# OpenProg-18F2550.net
KiCad netlist of a schematic drawn in EAGLE
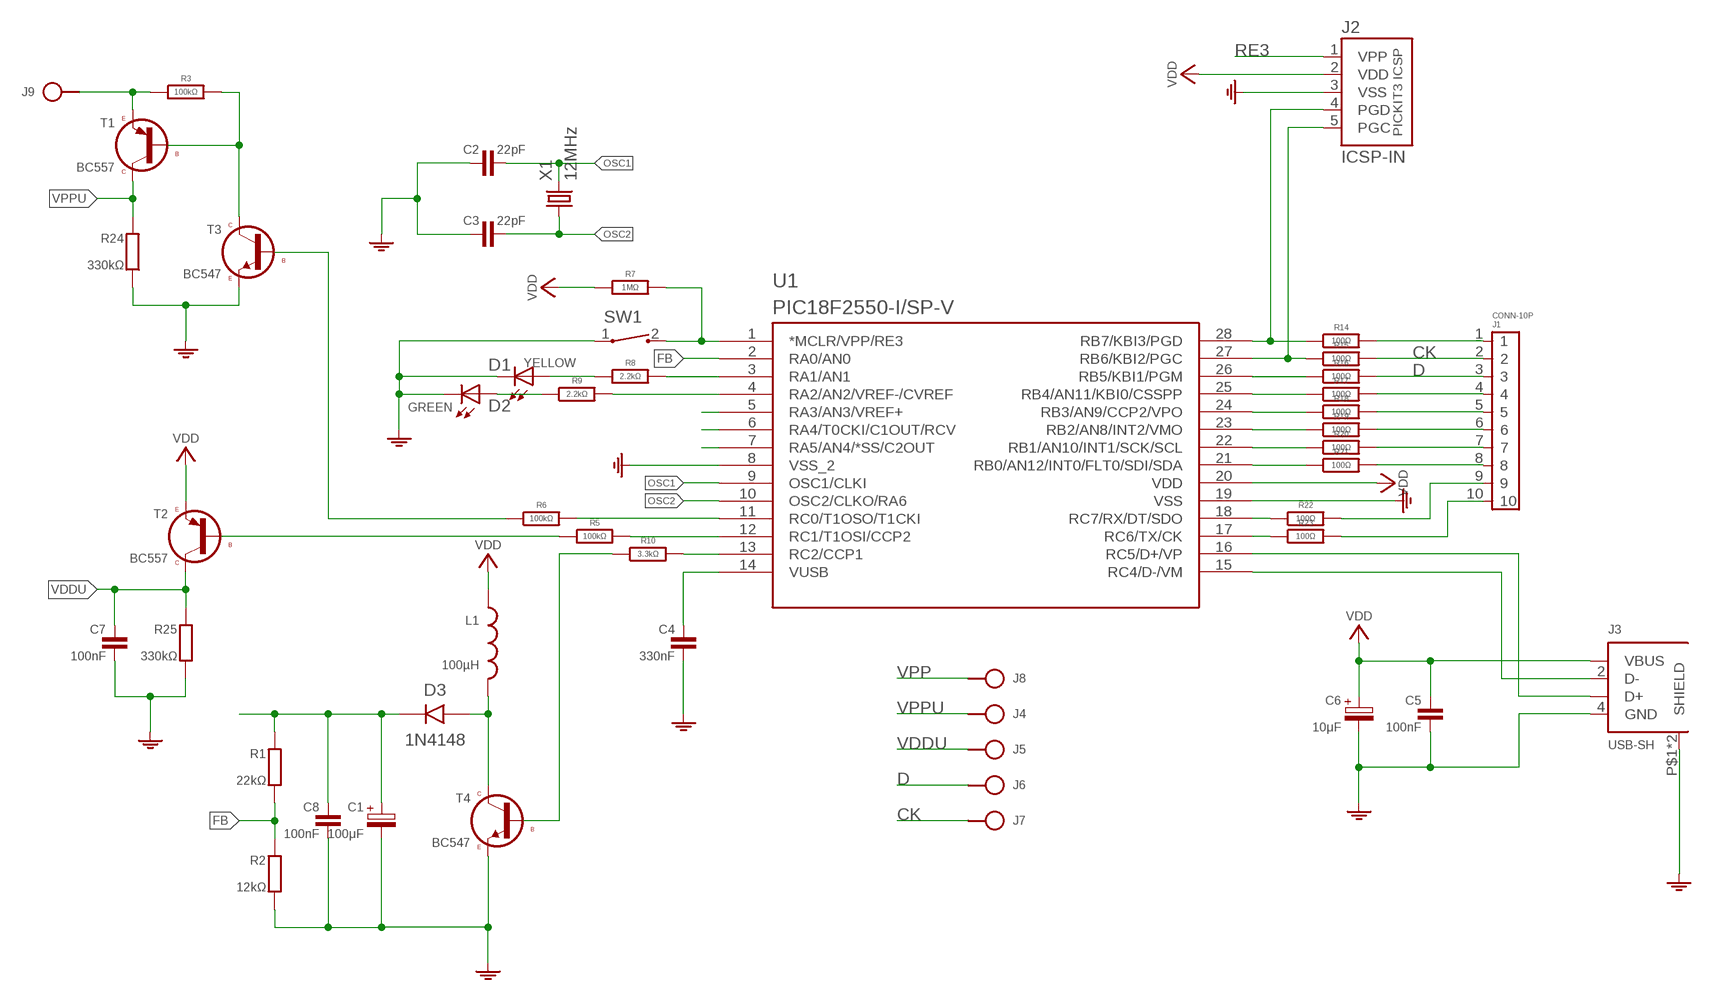
[diagram p0: schematic, sheet 1]

(export (version "E")
  (design (tool "Eeschema 10.0.6"))
  (components
    (comp (ref "C1")
      (value "100μF")
      (footprint "eagle-import:E5-5")
      (libsource (lib "eagle-import") (part "CPOLE5-5"))
    )
    (comp (ref "C2")
      (value "22pF")
      (footprint "eagle-import:C025-015X024")
      (libsource (lib "eagle-import") (part "C-H025-015X024"))
    )
    (comp (ref "C3")
      (value "22pF")
      (footprint "eagle-import:C025-015X024")
      (libsource (lib "eagle-import") (part "C-H025-015X024"))
    )
    (comp (ref "C4")
      (value "330nF")
      (footprint "eagle-import:C050-030X075")
      (libsource (lib "eagle-import") (part "C050-030X075"))
    )
    (comp (ref "C5")
      (value "100nF")
      (footprint "eagle-import:C050-025X075")
      (libsource (lib "eagle-import") (part "C050-025X075"))
    )
    (comp (ref "C6")
      (value "10μF")
      (footprint "eagle-import:E5-5")
      (libsource (lib "eagle-import") (part "CPOLE5-5"))
    )
    (comp (ref "C7")
      (value "100nF")
      (footprint "eagle-import:C050-025X075")
      (libsource (lib "eagle-import") (part "C050-025X075"))
    )
    (comp (ref "C8")
      (value "100nF")
      (footprint "eagle-import:C050-025X075")
      (libsource (lib "eagle-import") (part "C050-025X075"))
    )
    (comp (ref "D1")
      (value "YELLOW")
      (footprint "eagle-import:LED_3MM")
      (libsource (lib "eagle-import") (part "LED-3MM"))
    )
    (comp (ref "D2")
      (value "GREEN")
      (footprint "eagle-import:LED_3MM")
      (libsource (lib "eagle-import") (part "LED-3MM"))
    )
    (comp (ref "D3")
      (value "1N4148")
      (footprint "eagle-import:DO34-7")
      (libsource (lib "eagle-import") (part "1N4148-HDO34-7"))
    )
    (comp (ref "J1")
      (value "CONN-10P")
      (footprint "eagle-import:CONN-10P")
      (libsource (lib "eagle-import") (part "CONN-10P"))
    )
    (comp (ref "J2")
      (value "ICSP-IN")
      (footprint "eagle-import:PIC-PK3")
      (libsource (lib "eagle-import") (part "PICKIT3-ICSP-PK3"))
    )
    (comp (ref "J3")
      (value "USB-SH")
      (footprint "eagle-import:USB-B-PRINT")
      (libsource (lib "eagle-import") (part "USB-SH"))
    )
    (comp (ref "J4")
      (value "HPORT")
      (footprint "eagle-import:SPAD")
      (libsource (lib "eagle-import") (part "HPORT"))
    )
    (comp (ref "J5")
      (value "HPORT")
      (footprint "eagle-import:SPAD")
      (libsource (lib "eagle-import") (part "HPORT"))
    )
    (comp (ref "J6")
      (value "HPORT")
      (footprint "eagle-import:SPAD")
      (libsource (lib "eagle-import") (part "HPORT"))
    )
    (comp (ref "J7")
      (value "HPORT")
      (footprint "eagle-import:SPAD")
      (libsource (lib "eagle-import") (part "HPORT"))
    )
    (comp (ref "J8")
      (value "HPORT")
      (footprint "eagle-import:SPAD")
      (libsource (lib "eagle-import") (part "HPORT"))
    )
    (comp (ref "J9")
      (value "HPORT")
      (footprint "eagle-import:SPAD")
      (libsource (lib "eagle-import") (part "HPORT"))
    )
    (comp (ref "L1")
      (value "100µH")
      (footprint "eagle-import:L-03_10V")
      (libsource (lib "eagle-import") (part "L02/10"))
    )
    (comp (ref "R1")
      (value "22kΩ")
      (footprint "eagle-import:0204_10-V")
      (libsource (lib "eagle-import") (part "R0204/10-V"))
    )
    (comp (ref "R2")
      (value "12kΩ")
      (footprint "eagle-import:0204_10-V")
      (libsource (lib "eagle-import") (part "R0204/10-V"))
    )
    (comp (ref "R3")
      (value "100kΩ")
      (footprint "eagle-import:0204_2")
      (libsource (lib "eagle-import") (part "R-H0204/2"))
    )
    (comp (ref "R5")
      (value "100kΩ")
      (footprint "eagle-import:0204_10")
      (libsource (lib "eagle-import") (part "R-H0204/10"))
    )
    (comp (ref "R6")
      (value "100kΩ")
      (footprint "eagle-import:0204_10")
      (libsource (lib "eagle-import") (part "R-H0204/10"))
    )
    (comp (ref "R7")
      (value "1MΩ")
      (footprint "eagle-import:0204_10")
      (libsource (lib "eagle-import") (part "R-H0204/10"))
    )
    (comp (ref "R8")
      (value "2.2kΩ")
      (footprint "eagle-import:0204_10")
      (libsource (lib "eagle-import") (part "R-H0204/10"))
    )
    (comp (ref "R9")
      (value "2.2kΩ")
      (footprint "eagle-import:0204_10")
      (libsource (lib "eagle-import") (part "R-H0204/10"))
    )
    (comp (ref "R10")
      (value "3.3kΩ")
      (footprint "eagle-import:0204_10")
      (libsource (lib "eagle-import") (part "R-H0204/10"))
    )
    (comp (ref "R14")
      (value "100Ω")
      (footprint "eagle-import:0204_10")
      (libsource (lib "eagle-import") (part "R-H0204/10"))
    )
    (comp (ref "R15")
      (value "100Ω")
      (footprint "eagle-import:0204_10")
      (libsource (lib "eagle-import") (part "R-H0204/10"))
    )
    (comp (ref "R16")
      (value "100Ω")
      (footprint "eagle-import:0204_10")
      (libsource (lib "eagle-import") (part "R-H0204/10"))
    )
    (comp (ref "R17")
      (value "100Ω")
      (footprint "eagle-import:0204_10")
      (libsource (lib "eagle-import") (part "R-H0204/10"))
    )
    (comp (ref "R18")
      (value "100Ω")
      (footprint "eagle-import:0204_10")
      (libsource (lib "eagle-import") (part "R-H0204/10"))
    )
    (comp (ref "R19")
      (value "100Ω")
      (footprint "eagle-import:0204_10")
      (libsource (lib "eagle-import") (part "R-H0204/10"))
    )
    (comp (ref "R20")
      (value "100Ω")
      (footprint "eagle-import:0204_10")
      (libsource (lib "eagle-import") (part "R-H0204/10"))
    )
    (comp (ref "R21")
      (value "100Ω")
      (footprint "eagle-import:0204_10")
      (libsource (lib "eagle-import") (part "R-H0204/10"))
    )
    (comp (ref "R22")
      (value "100Ω")
      (footprint "eagle-import:0204_10")
      (libsource (lib "eagle-import") (part "R-H0204/10"))
    )
    (comp (ref "R23")
      (value "100Ω")
      (footprint "eagle-import:0204_10")
      (libsource (lib "eagle-import") (part "R-H0204/10"))
    )
    (comp (ref "R24")
      (value "330kΩ")
      (footprint "eagle-import:0204_10-V")
      (libsource (lib "eagle-import") (part "R0204/10-V"))
    )
    (comp (ref "R25")
      (value "330kΩ")
      (footprint "eagle-import:0204_10-V")
      (libsource (lib "eagle-import") (part "R0204/10-V"))
    )
    (comp (ref "SW1")
      (value "PUSHBUTTON-P1T")
      (footprint "eagle-import:PB-1P1T")
      (libsource (lib "eagle-import") (part "PUSHBUTTON-P1T"))
    )
    (comp (ref "T1")
      (value "BC557")
      (footprint "eagle-import:TO92-CBE-A")
      (libsource (lib "eagle-import") (part "BC557CBE-A"))
    )
    (comp (ref "T2")
      (value "BC557")
      (footprint "eagle-import:TO92-CBE-A")
      (libsource (lib "eagle-import") (part "BC557CBE-A"))
    )
    (comp (ref "T3")
      (value "BC547")
      (footprint "eagle-import:TO92-CBE-A")
      (libsource (lib "eagle-import") (part "BC547-A"))
    )
    (comp (ref "T4")
      (value "BC547")
      (footprint "eagle-import:TO92-CBE-A")
      (libsource (lib "eagle-import") (part "BC547-A"))
    )
    (comp (ref "U1")
      (value "PIC18F2550-I/SP-V")
      (footprint "eagle-import:DIL28-3_V")
      (libsource (lib "eagle-import") (part "PIC18F2550-I/SP-V"))
    )
    (comp (ref "X1")
      (value "12MHz")
      (footprint "eagle-import:HC49")
      (libsource (lib "eagle-import") (part "CRYSTALHC49"))
    )
  )
  (nets
    (net (code "1") (name "/CK") (class "Default")
      (node (ref "J1") (pin "2") (pinfunction "2_2") (pintype "passive"))
      (node (ref "J7") (pin "1") (pinfunction "P$1_1") (pintype "passive"))
      (node (ref "R15") (pin "2") (pinfunction "2_2") (pintype "passive"))
    )
    (net (code "2") (name "/D") (class "Default")
      (node (ref "J1") (pin "3") (pinfunction "3_3") (pintype "passive"))
      (node (ref "J6") (pin "1") (pinfunction "P$1_1") (pintype "passive"))
      (node (ref "R16") (pin "2") (pinfunction "2_2") (pintype "passive"))
    )
    (net (code "3") (name "/RE3") (class "Default")
      (node (ref "J2") (pin "1") (pinfunction "VPP_1") (pintype "passive"))
      (node (ref "R7") (pin "2") (pinfunction "2_2") (pintype "passive"))
      (node (ref "SW1") (pin "2") (pinfunction "2_2") (pintype "passive"))
      (node (ref "U1") (pin "1") (pinfunction "*MCLR/VPP/RE3_1") (pintype "passive"))
    )
    (net (code "4") (name "/VPP") (class "Default")
      (node (ref "C1") (pin "+") (pinfunction "+_+") (pintype "passive"))
      (node (ref "C8") (pin "1") (pinfunction "1_1") (pintype "passive"))
      (node (ref "D3") (pin "C") (pinfunction "C_C") (pintype "passive"))
      (node (ref "J8") (pin "1") (pinfunction "P$1_1") (pintype "passive"))
      (node (ref "R1") (pin "1") (pinfunction "2_1") (pintype "passive"))
    )
    (net (code "5") (name "FB") (class "Default")
      (node (ref "R1") (pin "2") (pinfunction "1_2") (pintype "passive"))
      (node (ref "R2") (pin "1") (pinfunction "2_1") (pintype "passive"))
      (node (ref "U1") (pin "2") (pinfunction "RA0/AN0_2") (pintype "passive"))
    )
    (net (code "6") (name "GND") (class "Default")
      (node (ref "C1") (pin "-") (pinfunction "-_-") (pintype "passive"))
      (node (ref "C2") (pin "1") (pinfunction "1_1") (pintype "passive"))
      (node (ref "C3") (pin "1") (pinfunction "1_1") (pintype "passive"))
      (node (ref "C4") (pin "2") (pinfunction "2_2") (pintype "passive"))
      (node (ref "C5") (pin "2") (pinfunction "2_2") (pintype "passive"))
      (node (ref "C6") (pin "-") (pinfunction "-_-") (pintype "passive"))
      (node (ref "C7") (pin "2") (pinfunction "2_2") (pintype "passive"))
      (node (ref "C8") (pin "2") (pinfunction "2_2") (pintype "passive"))
      (node (ref "D1") (pin "K") (pinfunction "C_K") (pintype "passive"))
      (node (ref "D2") (pin "K") (pinfunction "C_K") (pintype "passive"))
      (node (ref "J2") (pin "3") (pinfunction "VSS_3") (pintype "passive"))
      (node (ref "J3") (pin "4") (pinfunction "GND_4") (pintype "bidirectional"))
      (node (ref "J3") (pin "P$1") (pinfunction "SHIELD_P$1") (pintype "bidirectional"))
      (node (ref "J3") (pin "P$2") (pinfunction "SHIELD_P$2") (pintype "bidirectional"))
      (node (ref "R2") (pin "2") (pinfunction "1_2") (pintype "passive"))
      (node (ref "R24") (pin "2") (pinfunction "1_2") (pintype "passive"))
      (node (ref "R25") (pin "2") (pinfunction "1_2") (pintype "passive"))
      (node (ref "SW1") (pin "1") (pinfunction "1_1") (pintype "passive"))
      (node (ref "T3") (pin "3") (pinfunction "E_3") (pintype "passive"))
      (node (ref "T4") (pin "3") (pinfunction "E_3") (pintype "passive"))
      (node (ref "U1") (pin "19") (pinfunction "VSS_19") (pintype "passive"))
      (node (ref "U1") (pin "8") (pinfunction "VSS_2_8") (pintype "passive"))
    )
    (net (code "7") (name "Net-(D1-PadA)") (class "Default")
      (node (ref "D1") (pin "A") (pinfunction "A_A") (pintype "passive"))
      (node (ref "R8") (pin "1") (pinfunction "1_1") (pintype "passive"))
    )
    (net (code "8") (name "Net-(D2-PadA)") (class "Default")
      (node (ref "D2") (pin "A") (pinfunction "A_A") (pintype "passive"))
      (node (ref "R9") (pin "1") (pinfunction "1_1") (pintype "passive"))
    )
    (net (code "9") (name "Net-(J1-Pad1)") (class "Default")
      (node (ref "J1") (pin "1") (pinfunction "1_1") (pintype "passive"))
      (node (ref "R14") (pin "2") (pinfunction "2_2") (pintype "passive"))
    )
    (net (code "10") (name "Net-(J1-Pad4)") (class "Default")
      (node (ref "J1") (pin "4") (pinfunction "4_4") (pintype "passive"))
      (node (ref "R17") (pin "2") (pinfunction "2_2") (pintype "passive"))
    )
    (net (code "11") (name "Net-(J1-Pad5)") (class "Default")
      (node (ref "J1") (pin "5") (pinfunction "5_5") (pintype "passive"))
      (node (ref "R18") (pin "2") (pinfunction "2_2") (pintype "passive"))
    )
    (net (code "12") (name "Net-(J1-Pad6)") (class "Default")
      (node (ref "J1") (pin "6") (pinfunction "6_6") (pintype "passive"))
      (node (ref "R19") (pin "2") (pinfunction "2_2") (pintype "passive"))
    )
    (net (code "13") (name "Net-(J1-Pad7)") (class "Default")
      (node (ref "J1") (pin "7") (pinfunction "7_7") (pintype "passive"))
      (node (ref "R20") (pin "2") (pinfunction "2_2") (pintype "passive"))
    )
    (net (code "14") (name "Net-(J1-Pad8)") (class "Default")
      (node (ref "J1") (pin "8") (pinfunction "8_8") (pintype "passive"))
      (node (ref "R21") (pin "2") (pinfunction "2_2") (pintype "passive"))
    )
    (net (code "15") (name "Net-(J1-Pad9)") (class "Default")
      (node (ref "J1") (pin "9") (pinfunction "9_9") (pintype "passive"))
      (node (ref "R22") (pin "2") (pinfunction "2_2") (pintype "passive"))
    )
    (net (code "16") (name "Net-(J1-Pad10)") (class "Default")
      (node (ref "J1") (pin "10") (pinfunction "10_10") (pintype "passive"))
      (node (ref "R23") (pin "2") (pinfunction "2_2") (pintype "passive"))
    )
    (net (code "17") (name "Net-(J2-PGC)") (class "Default")
      (node (ref "J2") (pin "5") (pinfunction "PGC_5") (pintype "passive"))
      (node (ref "R15") (pin "1") (pinfunction "1_1") (pintype "passive"))
      (node (ref "U1") (pin "27") (pinfunction "RB6/KBI2/PGC_27") (pintype "passive"))
    )
    (net (code "18") (name "Net-(J2-PGD)") (class "Default")
      (node (ref "J2") (pin "4") (pinfunction "PGD_4") (pintype "passive"))
      (node (ref "R14") (pin "1") (pinfunction "1_1") (pintype "passive"))
      (node (ref "U1") (pin "28") (pinfunction "RB7/KBI3/PGD_28") (pintype "passive"))
    )
    (net (code "19") (name "Net-(J3-D+)") (class "Default")
      (node (ref "J3") (pin "3") (pinfunction "D+_3") (pintype "bidirectional"))
      (node (ref "U1") (pin "16") (pinfunction "RC5/D+/VP_16") (pintype "passive"))
    )
    (net (code "20") (name "Net-(J3-D-)") (class "Default")
      (node (ref "J3") (pin "2") (pinfunction "D-_2") (pintype "bidirectional"))
      (node (ref "U1") (pin "15") (pinfunction "RC4/D-/VM_15") (pintype "passive"))
    )
    (net (code "21") (name "Net-(J9-P$1)") (class "Default")
      (node (ref "J9") (pin "1") (pinfunction "P$1_1") (pintype "passive"))
      (node (ref "R3") (pin "1") (pinfunction "1_1") (pintype "passive"))
      (node (ref "T1") (pin "3") (pinfunction "E_3") (pintype "passive"))
    )
    (net (code "22") (name "Net-(T1-B)") (class "Default")
      (node (ref "R3") (pin "2") (pinfunction "2_2") (pintype "passive"))
      (node (ref "T1") (pin "2") (pinfunction "B_2") (pintype "passive"))
      (node (ref "T3") (pin "1") (pinfunction "C_1") (pintype "passive"))
    )
    (net (code "23") (name "Net-(T2-B)") (class "Default")
      (node (ref "R5") (pin "1") (pinfunction "1_1") (pintype "passive"))
      (node (ref "T2") (pin "2") (pinfunction "B_2") (pintype "passive"))
    )
    (net (code "24") (name "Net-(T3-B)") (class "Default")
      (node (ref "R6") (pin "1") (pinfunction "1_1") (pintype "passive"))
      (node (ref "T3") (pin "2") (pinfunction "B_2") (pintype "passive"))
    )
    (net (code "25") (name "Net-(T4-B)") (class "Default")
      (node (ref "R10") (pin "1") (pinfunction "1_1") (pintype "passive"))
      (node (ref "T4") (pin "2") (pinfunction "B_2") (pintype "passive"))
    )
    (net (code "26") (name "Net-(T4-C)") (class "Default")
      (node (ref "D3") (pin "A") (pinfunction "A_A") (pintype "passive"))
      (node (ref "L1") (pin "2") (pinfunction "2_2") (pintype "passive"))
      (node (ref "T4") (pin "1") (pinfunction "C_1") (pintype "passive"))
    )
    (net (code "27") (name "Net-(U1-RA1{slash}AN1)") (class "Default")
      (node (ref "R8") (pin "2") (pinfunction "2_2") (pintype "passive"))
      (node (ref "U1") (pin "3") (pinfunction "RA1/AN1_3") (pintype "passive"))
    )
    (net (code "28") (name "Net-(U1-RA2{slash}AN2{slash}VREF-{slash}CVREF)") (class "Default")
      (node (ref "R9") (pin "2") (pinfunction "2_2") (pintype "passive"))
      (node (ref "U1") (pin "4") (pinfunction "RA2/AN2/VREF-/CVREF_4") (pintype "passive"))
    )
    (net (code "29") (name "Net-(U1-RB0{slash}AN12{slash}INT0{slash}FLT0{slash}SDI{slash}SDA)") (class "Default")
      (node (ref "R21") (pin "1") (pinfunction "1_1") (pintype "passive"))
      (node (ref "U1") (pin "21") (pinfunction "RB0/AN12/INT0/FLT0/SDI/SDA_21") (pintype "passive"))
    )
    (net (code "30") (name "Net-(U1-RB1{slash}AN10{slash}INT1{slash}SCK{slash}SCL)") (class "Default")
      (node (ref "R20") (pin "1") (pinfunction "1_1") (pintype "passive"))
      (node (ref "U1") (pin "22") (pinfunction "RB1/AN10/INT1/SCK/SCL_22") (pintype "passive"))
    )
    (net (code "31") (name "Net-(U1-RB2{slash}AN8{slash}INT2{slash}VMO)") (class "Default")
      (node (ref "R19") (pin "1") (pinfunction "1_1") (pintype "passive"))
      (node (ref "U1") (pin "23") (pinfunction "RB2/AN8/INT2/VMO_23") (pintype "passive"))
    )
    (net (code "32") (name "Net-(U1-RB3{slash}AN9{slash}CCP2{slash}VPO)") (class "Default")
      (node (ref "R18") (pin "1") (pinfunction "1_1") (pintype "passive"))
      (node (ref "U1") (pin "24") (pinfunction "RB3/AN9/CCP2/VPO_24") (pintype "passive"))
    )
    (net (code "33") (name "Net-(U1-RB4{slash}AN11{slash}KBI0{slash}CSSPP)") (class "Default")
      (node (ref "R17") (pin "1") (pinfunction "1_1") (pintype "passive"))
      (node (ref "U1") (pin "25") (pinfunction "RB4/AN11/KBI0/CSSPP_25") (pintype "passive"))
    )
    (net (code "34") (name "Net-(U1-RB5{slash}KBI1{slash}PGM)") (class "Default")
      (node (ref "R16") (pin "1") (pinfunction "1_1") (pintype "passive"))
      (node (ref "U1") (pin "26") (pinfunction "RB5/KBI1/PGM_26") (pintype "passive"))
    )
    (net (code "35") (name "Net-(U1-RC0{slash}T1OSO{slash}T1CKI)") (class "Default")
      (node (ref "R6") (pin "2") (pinfunction "2_2") (pintype "passive"))
      (node (ref "U1") (pin "11") (pinfunction "RC0/T1OSO/T1CKI_11") (pintype "passive"))
    )
    (net (code "36") (name "Net-(U1-RC1{slash}T1OSI{slash}CCP2)") (class "Default")
      (node (ref "R5") (pin "2") (pinfunction "2_2") (pintype "passive"))
      (node (ref "U1") (pin "12") (pinfunction "RC1/T1OSI/CCP2_12") (pintype "passive"))
    )
    (net (code "37") (name "Net-(U1-RC2{slash}CCP1)") (class "Default")
      (node (ref "R10") (pin "2") (pinfunction "2_2") (pintype "passive"))
      (node (ref "U1") (pin "13") (pinfunction "RC2/CCP1_13") (pintype "passive"))
    )
    (net (code "38") (name "Net-(U1-RC6{slash}TX{slash}CK)") (class "Default")
      (node (ref "R23") (pin "1") (pinfunction "1_1") (pintype "passive"))
      (node (ref "U1") (pin "17") (pinfunction "RC6/TX/CK_17") (pintype "passive"))
    )
    (net (code "39") (name "Net-(U1-RC7{slash}RX{slash}DT{slash}SDO)") (class "Default")
      (node (ref "R22") (pin "1") (pinfunction "1_1") (pintype "passive"))
      (node (ref "U1") (pin "18") (pinfunction "RC7/RX/DT/SDO_18") (pintype "passive"))
    )
    (net (code "40") (name "Net-(U1-VUSB)") (class "Default")
      (node (ref "C4") (pin "1") (pinfunction "1_1") (pintype "passive"))
      (node (ref "U1") (pin "14") (pinfunction "VUSB_14") (pintype "passive"))
    )
    (net (code "41") (name "OSC1") (class "Default")
      (node (ref "C2") (pin "2") (pinfunction "2_2") (pintype "passive"))
      (node (ref "U1") (pin "9") (pinfunction "OSC1/CLKI_9") (pintype "passive"))
      (node (ref "X1") (pin "2") (pinfunction "2_2") (pintype "passive"))
    )
    (net (code "42") (name "OSC2") (class "Default")
      (node (ref "C3") (pin "2") (pinfunction "2_2") (pintype "passive"))
      (node (ref "U1") (pin "10") (pinfunction "OSC2/CLKO/RA6_10") (pintype "passive"))
      (node (ref "X1") (pin "1") (pinfunction "1_1") (pintype "passive"))
    )
    (net (code "43") (name "VDD") (class "Default")
      (node (ref "C5") (pin "1") (pinfunction "1_1") (pintype "passive"))
      (node (ref "C6") (pin "+") (pinfunction "+_+") (pintype "passive"))
      (node (ref "J2") (pin "2") (pinfunction "VDD_2") (pintype "passive"))
      (node (ref "J3") (pin "1") (pinfunction "VBUS_1") (pintype "bidirectional"))
      (node (ref "L1") (pin "1") (pinfunction "1_1") (pintype "passive"))
      (node (ref "R7") (pin "1") (pinfunction "1_1") (pintype "passive"))
      (node (ref "T2") (pin "3") (pinfunction "E_3") (pintype "passive"))
      (node (ref "U1") (pin "20") (pinfunction "VDD_20") (pintype "passive"))
    )
    (net (code "44") (name "VDDU") (class "Default")
      (node (ref "C7") (pin "1") (pinfunction "1_1") (pintype "passive"))
      (node (ref "J5") (pin "1") (pinfunction "P$1_1") (pintype "passive"))
      (node (ref "R25") (pin "1") (pinfunction "2_1") (pintype "passive"))
      (node (ref "T2") (pin "1") (pinfunction "C_1") (pintype "passive"))
    )
    (net (code "45") (name "VPPU") (class "Default")
      (node (ref "J4") (pin "1") (pinfunction "P$1_1") (pintype "passive"))
      (node (ref "R24") (pin "1") (pinfunction "2_1") (pintype "passive"))
      (node (ref "T1") (pin "1") (pinfunction "C_1") (pintype "passive"))
    )
    (net (code "46") (name "unconnected-(U1-RA3{slash}AN3{slash}VREF+-Pad5)") (class "Default")
      (node (ref "U1") (pin "5") (pinfunction "RA3/AN3/VREF+_5") (pintype "passive"))
    )
    (net (code "47") (name "unconnected-(U1-RA4{slash}T0CKI{slash}C1OUT{slash}RCV-Pad6)") (class "Default")
      (node (ref "U1") (pin "6") (pinfunction "RA4/T0CKI/C1OUT/RCV_6") (pintype "passive"))
    )
    (net (code "48") (name "unconnected-(U1-RA5{slash}AN4{slash}*SS{slash}C2OUT-Pad7)") (class "Default")
      (node (ref "U1") (pin "7") (pinfunction "RA5/AN4/*SS/C2OUT_7") (pintype "passive"))
    )
  )
)
